# template_25x45.net
KiCad netlist of a schematic drawn in EAGLE
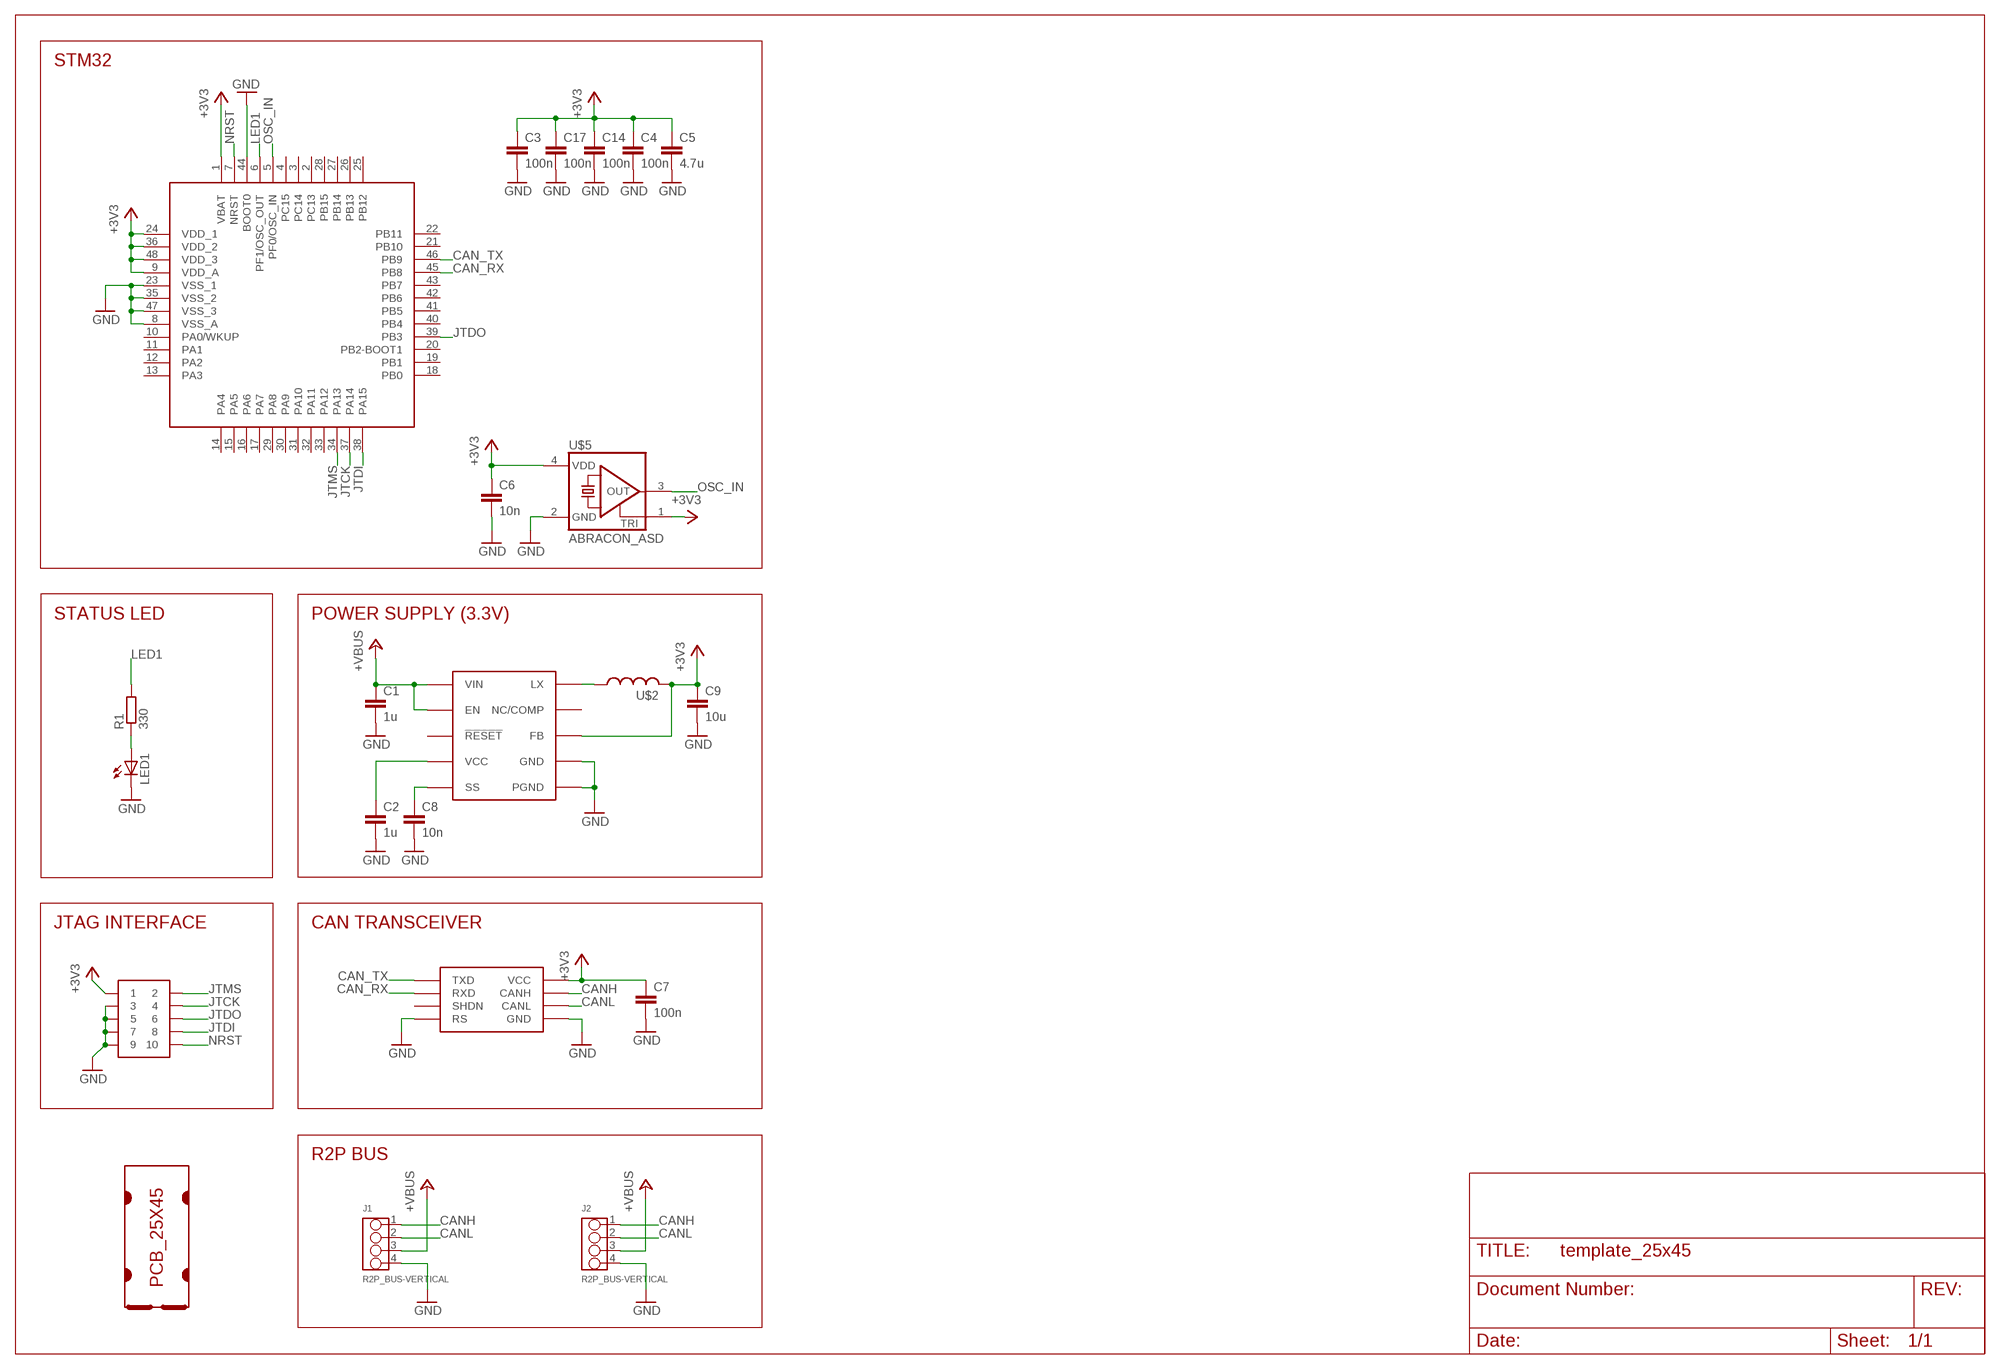
[diagram p0: schematic, sheet 1]

(export (version "E")
  (design (tool "Eeschema 10.0.6"))
  (components
    (comp (ref "C1")
      (value "1u")
      (footprint "eagle-import:C1206")
      (libsource (lib "eagle-import") (part "C1206"))
    )
    (comp (ref "C2")
      (value "1u")
      (footprint "eagle-import:C0603")
      (libsource (lib "eagle-import") (part "C0603"))
    )
    (comp (ref "C3")
      (value "100n")
      (footprint "eagle-import:C0603")
      (libsource (lib "eagle-import") (part "C0603"))
    )
    (comp (ref "C4")
      (value "100n")
      (footprint "eagle-import:C0603")
      (libsource (lib "eagle-import") (part "C0603"))
    )
    (comp (ref "C5")
      (value "4.7u")
      (footprint "eagle-import:C0805")
      (libsource (lib "eagle-import") (part "C0805"))
    )
    (comp (ref "C6")
      (value "10n")
      (footprint "eagle-import:C0603")
      (libsource (lib "eagle-import") (part "C0603"))
    )
    (comp (ref "C7")
      (value "100n")
      (footprint "eagle-import:C0603")
      (libsource (lib "eagle-import") (part "C0603"))
    )
    (comp (ref "C8")
      (value "10n")
      (footprint "eagle-import:C0603")
      (libsource (lib "eagle-import") (part "C0603"))
    )
    (comp (ref "C9")
      (value "10u")
      (footprint "eagle-import:C0805")
      (libsource (lib "eagle-import") (part "C0805"))
    )
    (comp (ref "C14")
      (value "100n")
      (footprint "eagle-import:C0603")
      (libsource (lib "eagle-import") (part "C0603"))
    )
    (comp (ref "C17")
      (value "100n")
      (footprint "eagle-import:C0603")
      (libsource (lib "eagle-import") (part "C0603"))
    )
    (comp (ref "J1")
      (value "R2P_BUS-VERTICAL")
      (footprint "eagle-import:OPL-EAGLE-LIBRARY_4P-2.0")
      (libsource (lib "eagle-import") (part "R2P_BUS-VERTICAL"))
    )
    (comp (ref "J2")
      (value "R2P_BUS-VERTICAL")
      (footprint "eagle-import:OPL-EAGLE-LIBRARY_4P-2.0")
      (libsource (lib "eagle-import") (part "R2P_BUS-VERTICAL"))
    )
    (comp (ref "LED1")
      (value "LED0805")
      (footprint "eagle-import:CHIPLED_0805")
      (libsource (lib "eagle-import") (part "LED0805"))
    )
    (comp (ref "R1")
      (value "330")
      (footprint "eagle-import:R0603")
      (libsource (lib "eagle-import") (part "R0603"))
    )
    (comp (ref "SOT1")
      (value "MAX3051EKA")
      (footprint "eagle-import:SOT23-8L")
      (libsource (lib "eagle-import") (part "MAX3051EKA"))
    )
    (comp (ref "U$1")
      (value "PCB_25X45")
      (footprint "eagle-import:25X45")
      (libsource (lib "eagle-import") (part "PCB_25X45"))
    )
    (comp (ref "U$2")
      (value "LPS4018")
      (footprint "eagle-import:COILCRAFT_LPS4018")
      (libsource (lib "eagle-import") (part "LPS4018"))
    )
    (comp (ref "U$3")
      (value "MAX17501")
      (footprint "eagle-import:TDFN-10")
      (libsource (lib "eagle-import") (part "MAX17501"))
    )
    (comp (ref "U$4")
      (value "JTAG-TH")
      (footprint "eagle-import:SAMTEC_FTSH-105-TH")
      (libsource (lib "eagle-import") (part "JTAG-TH"))
    )
    (comp (ref "U$5")
      (value "ABRACON_ASD")
      (footprint "eagle-import:ABRACON_2.5X2")
      (libsource (lib "eagle-import") (part "ABRACON_ASD"))
    )
    (comp (ref "U$6")
      (value "STM32F303CTX")
      (footprint "eagle-import:LQFP48")
      (libsource (lib "eagle-import") (part "STM32F303CTX"))
    )
  )
  (nets
    (net (code "1") (name "+3V3") (class "Default")
      (node (ref "C14") (pin "1") (pinfunction "1_1") (pintype "passive"))
      (node (ref "C17") (pin "1") (pinfunction "1_1") (pintype "passive"))
      (node (ref "C3") (pin "1") (pinfunction "1_1") (pintype "passive"))
      (node (ref "C4") (pin "1") (pinfunction "1_1") (pintype "passive"))
      (node (ref "C5") (pin "1") (pinfunction "1_1") (pintype "passive"))
      (node (ref "C6") (pin "1") (pinfunction "1_1") (pintype "passive"))
      (node (ref "C7") (pin "1") (pinfunction "1_1") (pintype "passive"))
      (node (ref "C9") (pin "1") (pinfunction "1_1") (pintype "passive"))
      (node (ref "SOT1") (pin "3") (pinfunction "VCC_3") (pintype "bidirectional"))
      (node (ref "U$2") (pin "P$2") (pinfunction "2_P$2") (pintype "passive"))
      (node (ref "U$3") (pin "P$5") (pinfunction "FB_P$5") (pintype "bidirectional"))
      (node (ref "U$4") (pin "1") (pinfunction "1_1") (pintype "bidirectional"))
      (node (ref "U$5") (pin "1") (pinfunction "TRI_1") (pintype "input"))
      (node (ref "U$5") (pin "4") (pinfunction "VDD_4") (pintype "power_in"))
      (node (ref "U$6") (pin "1") (pinfunction "VBAT_1") (pintype "bidirectional"))
      (node (ref "U$6") (pin "24") (pinfunction "VDD_1_24") (pintype "bidirectional"))
      (node (ref "U$6") (pin "36") (pinfunction "VDD_2_36") (pintype "bidirectional"))
      (node (ref "U$6") (pin "48") (pinfunction "VDD_3_48") (pintype "bidirectional"))
      (node (ref "U$6") (pin "9") (pinfunction "VDD_A_9") (pintype "bidirectional"))
    )
    (net (code "2") (name "+VBUS") (class "Default")
      (node (ref "C1") (pin "1") (pinfunction "1_1") (pintype "passive"))
      (node (ref "J1") (pin "3") (pinfunction "3_3") (pintype "bidirectional"))
      (node (ref "J2") (pin "3") (pinfunction "3_3") (pintype "bidirectional"))
      (node (ref "U$3") (pin "P$2") (pinfunction "VIN_P$2") (pintype "bidirectional"))
      (node (ref "U$3") (pin "P$3") (pinfunction "EN_P$3") (pintype "bidirectional"))
    )
    (net (code "3") (name "/CANH") (class "Default")
      (node (ref "J1") (pin "1") (pinfunction "1_1") (pintype "bidirectional"))
      (node (ref "J2") (pin "1") (pinfunction "1_1") (pintype "bidirectional"))
      (node (ref "SOT1") (pin "7") (pinfunction "CANH_7") (pintype "bidirectional"))
    )
    (net (code "4") (name "/CANL") (class "Default")
      (node (ref "J1") (pin "2") (pinfunction "2_2") (pintype "bidirectional"))
      (node (ref "J2") (pin "2") (pinfunction "2_2") (pintype "bidirectional"))
      (node (ref "SOT1") (pin "6") (pinfunction "CANL_6") (pintype "bidirectional"))
    )
    (net (code "5") (name "/CAN_RX") (class "Default")
      (node (ref "SOT1") (pin "4") (pinfunction "RXD_4") (pintype "bidirectional"))
      (node (ref "U$6") (pin "45") (pinfunction "PB8_45") (pintype "bidirectional"))
    )
    (net (code "6") (name "/CAN_TX") (class "Default")
      (node (ref "SOT1") (pin "1") (pinfunction "TXD_1") (pintype "bidirectional"))
      (node (ref "U$6") (pin "46") (pinfunction "PB9_46") (pintype "bidirectional"))
    )
    (net (code "7") (name "/JTCK") (class "Default")
      (node (ref "U$4") (pin "4") (pinfunction "4_4") (pintype "bidirectional"))
      (node (ref "U$6") (pin "37") (pinfunction "PA14_37") (pintype "bidirectional"))
    )
    (net (code "8") (name "/JTDI") (class "Default")
      (node (ref "U$4") (pin "8") (pinfunction "8_8") (pintype "bidirectional"))
      (node (ref "U$6") (pin "38") (pinfunction "PA15_38") (pintype "bidirectional"))
    )
    (net (code "9") (name "/JTDO") (class "Default")
      (node (ref "U$4") (pin "6") (pinfunction "6_6") (pintype "bidirectional"))
      (node (ref "U$6") (pin "39") (pinfunction "PB3_39") (pintype "bidirectional"))
    )
    (net (code "10") (name "/JTMS") (class "Default")
      (node (ref "U$4") (pin "2") (pinfunction "2_2") (pintype "bidirectional"))
      (node (ref "U$6") (pin "34") (pinfunction "PA13_34") (pintype "bidirectional"))
    )
    (net (code "11") (name "/LED1") (class "Default")
      (node (ref "R1") (pin "2") (pinfunction "2_2") (pintype "passive"))
      (node (ref "U$6") (pin "6") (pinfunction "PF1/OSC_OUT_6") (pintype "bidirectional"))
    )
    (net (code "12") (name "/NRST") (class "Default")
      (node (ref "U$4") (pin "10") (pinfunction "10_10") (pintype "bidirectional"))
      (node (ref "U$6") (pin "7") (pinfunction "NRST_7") (pintype "bidirectional"))
    )
    (net (code "13") (name "/OSC_IN") (class "Default")
      (node (ref "U$5") (pin "3") (pinfunction "OUT_3") (pintype "output"))
      (node (ref "U$6") (pin "5") (pinfunction "PF0/OSC_IN_5") (pintype "bidirectional"))
    )
    (net (code "14") (name "GND") (class "Default")
      (node (ref "C1") (pin "2") (pinfunction "2_2") (pintype "passive"))
      (node (ref "C14") (pin "2") (pinfunction "2_2") (pintype "passive"))
      (node (ref "C17") (pin "2") (pinfunction "2_2") (pintype "passive"))
      (node (ref "C2") (pin "2") (pinfunction "2_2") (pintype "passive"))
      (node (ref "C3") (pin "2") (pinfunction "2_2") (pintype "passive"))
      (node (ref "C4") (pin "2") (pinfunction "2_2") (pintype "passive"))
      (node (ref "C5") (pin "2") (pinfunction "2_2") (pintype "passive"))
      (node (ref "C6") (pin "2") (pinfunction "2_2") (pintype "passive"))
      (node (ref "C7") (pin "2") (pinfunction "2_2") (pintype "passive"))
      (node (ref "C8") (pin "2") (pinfunction "2_2") (pintype "passive"))
      (node (ref "C9") (pin "2") (pinfunction "2_2") (pintype "passive"))
      (node (ref "J1") (pin "4") (pinfunction "4_4") (pintype "bidirectional"))
      (node (ref "J2") (pin "4") (pinfunction "4_4") (pintype "bidirectional"))
      (node (ref "LED1") (pin "C") (pinfunction "C_C") (pintype "passive"))
      (node (ref "SOT1") (pin "2") (pinfunction "GND_2") (pintype "bidirectional"))
      (node (ref "SOT1") (pin "8") (pinfunction "RS_8") (pintype "bidirectional"))
      (node (ref "U$3") (pin "P$1") (pinfunction "PGND_P$1") (pintype "bidirectional"))
      (node (ref "U$3") (pin "P$11") (pinfunction "PGND_P$11") (pintype "bidirectional"))
      (node (ref "U$3") (pin "P$9") (pinfunction "GND_P$9") (pintype "bidirectional"))
      (node (ref "U$4") (pin "3") (pinfunction "3_3") (pintype "bidirectional"))
      (node (ref "U$4") (pin "5") (pinfunction "5_5") (pintype "bidirectional"))
      (node (ref "U$4") (pin "7") (pinfunction "7_7") (pintype "bidirectional"))
      (node (ref "U$4") (pin "9") (pinfunction "9_9") (pintype "bidirectional"))
      (node (ref "U$5") (pin "2") (pinfunction "GND_2") (pintype "power_in"))
      (node (ref "U$6") (pin "23") (pinfunction "VSS_1_23") (pintype "bidirectional"))
      (node (ref "U$6") (pin "35") (pinfunction "VSS_2_35") (pintype "bidirectional"))
      (node (ref "U$6") (pin "44") (pinfunction "BOOT0_44") (pintype "bidirectional"))
      (node (ref "U$6") (pin "47") (pinfunction "VSS_3_47") (pintype "bidirectional"))
      (node (ref "U$6") (pin "8") (pinfunction "VSS_A_8") (pintype "bidirectional"))
    )
    (net (code "15") (name "Net-(LED1-PadA)") (class "Default")
      (node (ref "LED1") (pin "A") (pinfunction "A_A") (pintype "passive"))
      (node (ref "R1") (pin "1") (pinfunction "1_1") (pintype "passive"))
    )
    (net (code "16") (name "Net-(U$2-1)") (class "Default")
      (node (ref "U$2") (pin "P$1") (pinfunction "1_P$1") (pintype "passive"))
      (node (ref "U$3") (pin "P$10") (pinfunction "LX_P$10") (pintype "bidirectional"))
    )
    (net (code "17") (name "Net-(U$3-SS)") (class "Default")
      (node (ref "C8") (pin "1") (pinfunction "1_1") (pintype "passive"))
      (node (ref "U$3") (pin "P$6") (pinfunction "SS_P$6") (pintype "bidirectional"))
    )
    (net (code "18") (name "Net-(U$3-VCC)") (class "Default")
      (node (ref "C2") (pin "1") (pinfunction "1_1") (pintype "passive"))
      (node (ref "U$3") (pin "P$4") (pinfunction "VCC_P$4") (pintype "bidirectional"))
    )
    (net (code "19") (name "unconnected-(SOT1-SHDN-Pad5)") (class "Default")
      (node (ref "SOT1") (pin "5") (pinfunction "SHDN_5") (pintype "bidirectional"))
    )
    (net (code "20") (name "unconnected-(U$3-NC{slash}COMP-PadP$7)") (class "Default")
      (node (ref "U$3") (pin "P$7") (pinfunction "NC/COMP_P$7") (pintype "bidirectional"))
    )
    (net (code "21") (name "unconnected-(U$3-~{RESET}-PadP$8)") (class "Default")
      (node (ref "U$3") (pin "P$8") (pinfunction "~{RESET}_P$8") (pintype "bidirectional"))
    )
    (net (code "22") (name "unconnected-(U$6-PA0{slash}WKUP-Pad10)") (class "Default")
      (node (ref "U$6") (pin "10") (pinfunction "PA0/WKUP_10") (pintype "bidirectional"))
    )
    (net (code "23") (name "unconnected-(U$6-PA1-Pad11)") (class "Default")
      (node (ref "U$6") (pin "11") (pinfunction "PA1_11") (pintype "bidirectional"))
    )
    (net (code "24") (name "unconnected-(U$6-PA2-Pad12)") (class "Default")
      (node (ref "U$6") (pin "12") (pinfunction "PA2_12") (pintype "bidirectional"))
    )
    (net (code "25") (name "unconnected-(U$6-PA3-Pad13)") (class "Default")
      (node (ref "U$6") (pin "13") (pinfunction "PA3_13") (pintype "bidirectional"))
    )
    (net (code "26") (name "unconnected-(U$6-PA4-Pad14)") (class "Default")
      (node (ref "U$6") (pin "14") (pinfunction "PA4_14") (pintype "bidirectional"))
    )
    (net (code "27") (name "unconnected-(U$6-PA5-Pad15)") (class "Default")
      (node (ref "U$6") (pin "15") (pinfunction "PA5_15") (pintype "bidirectional"))
    )
    (net (code "28") (name "unconnected-(U$6-PA6-Pad16)") (class "Default")
      (node (ref "U$6") (pin "16") (pinfunction "PA6_16") (pintype "bidirectional"))
    )
    (net (code "29") (name "unconnected-(U$6-PA7-Pad17)") (class "Default")
      (node (ref "U$6") (pin "17") (pinfunction "PA7_17") (pintype "bidirectional"))
    )
    (net (code "30") (name "unconnected-(U$6-PA8-Pad29)") (class "Default")
      (node (ref "U$6") (pin "29") (pinfunction "PA8_29") (pintype "bidirectional"))
    )
    (net (code "31") (name "unconnected-(U$6-PA9-Pad30)") (class "Default")
      (node (ref "U$6") (pin "30") (pinfunction "PA9_30") (pintype "bidirectional"))
    )
    (net (code "32") (name "unconnected-(U$6-PA10-Pad31)") (class "Default")
      (node (ref "U$6") (pin "31") (pinfunction "PA10_31") (pintype "bidirectional"))
    )
    (net (code "33") (name "unconnected-(U$6-PA11-Pad32)") (class "Default")
      (node (ref "U$6") (pin "32") (pinfunction "PA11_32") (pintype "bidirectional"))
    )
    (net (code "34") (name "unconnected-(U$6-PA12-Pad33)") (class "Default")
      (node (ref "U$6") (pin "33") (pinfunction "PA12_33") (pintype "bidirectional"))
    )
    (net (code "35") (name "unconnected-(U$6-PB0-Pad18)") (class "Default")
      (node (ref "U$6") (pin "18") (pinfunction "PB0_18") (pintype "bidirectional"))
    )
    (net (code "36") (name "unconnected-(U$6-PB1-Pad19)") (class "Default")
      (node (ref "U$6") (pin "19") (pinfunction "PB1_19") (pintype "bidirectional"))
    )
    (net (code "37") (name "unconnected-(U$6-PB2-BOOT1-Pad20)") (class "Default")
      (node (ref "U$6") (pin "20") (pinfunction "PB2-BOOT1_20") (pintype "bidirectional"))
    )
    (net (code "38") (name "unconnected-(U$6-PB4-Pad40)") (class "Default")
      (node (ref "U$6") (pin "40") (pinfunction "PB4_40") (pintype "bidirectional"))
    )
    (net (code "39") (name "unconnected-(U$6-PB5-Pad41)") (class "Default")
      (node (ref "U$6") (pin "41") (pinfunction "PB5_41") (pintype "bidirectional"))
    )
    (net (code "40") (name "unconnected-(U$6-PB6-Pad42)") (class "Default")
      (node (ref "U$6") (pin "42") (pinfunction "PB6_42") (pintype "bidirectional"))
    )
    (net (code "41") (name "unconnected-(U$6-PB7-Pad43)") (class "Default")
      (node (ref "U$6") (pin "43") (pinfunction "PB7_43") (pintype "bidirectional"))
    )
    (net (code "42") (name "unconnected-(U$6-PB10-Pad21)") (class "Default")
      (node (ref "U$6") (pin "21") (pinfunction "PB10_21") (pintype "bidirectional"))
    )
    (net (code "43") (name "unconnected-(U$6-PB11-Pad22)") (class "Default")
      (node (ref "U$6") (pin "22") (pinfunction "PB11_22") (pintype "bidirectional"))
    )
    (net (code "44") (name "unconnected-(U$6-PB12-Pad25)") (class "Default")
      (node (ref "U$6") (pin "25") (pinfunction "PB12_25") (pintype "bidirectional"))
    )
    (net (code "45") (name "unconnected-(U$6-PB13-Pad26)") (class "Default")
      (node (ref "U$6") (pin "26") (pinfunction "PB13_26") (pintype "bidirectional"))
    )
    (net (code "46") (name "unconnected-(U$6-PB14-Pad27)") (class "Default")
      (node (ref "U$6") (pin "27") (pinfunction "PB14_27") (pintype "bidirectional"))
    )
    (net (code "47") (name "unconnected-(U$6-PB15-Pad28)") (class "Default")
      (node (ref "U$6") (pin "28") (pinfunction "PB15_28") (pintype "bidirectional"))
    )
    (net (code "48") (name "unconnected-(U$6-PC13-Pad2)") (class "Default")
      (node (ref "U$6") (pin "2") (pinfunction "PC13_2") (pintype "bidirectional"))
    )
    (net (code "49") (name "unconnected-(U$6-PC14-Pad3)") (class "Default")
      (node (ref "U$6") (pin "3") (pinfunction "PC14_3") (pintype "bidirectional"))
    )
    (net (code "50") (name "unconnected-(U$6-PC15-Pad4)") (class "Default")
      (node (ref "U$6") (pin "4") (pinfunction "PC15_4") (pintype "bidirectional"))
    )
  )
)
